# lednode.net
KiCad netlist of a schematic drawn in EAGLE
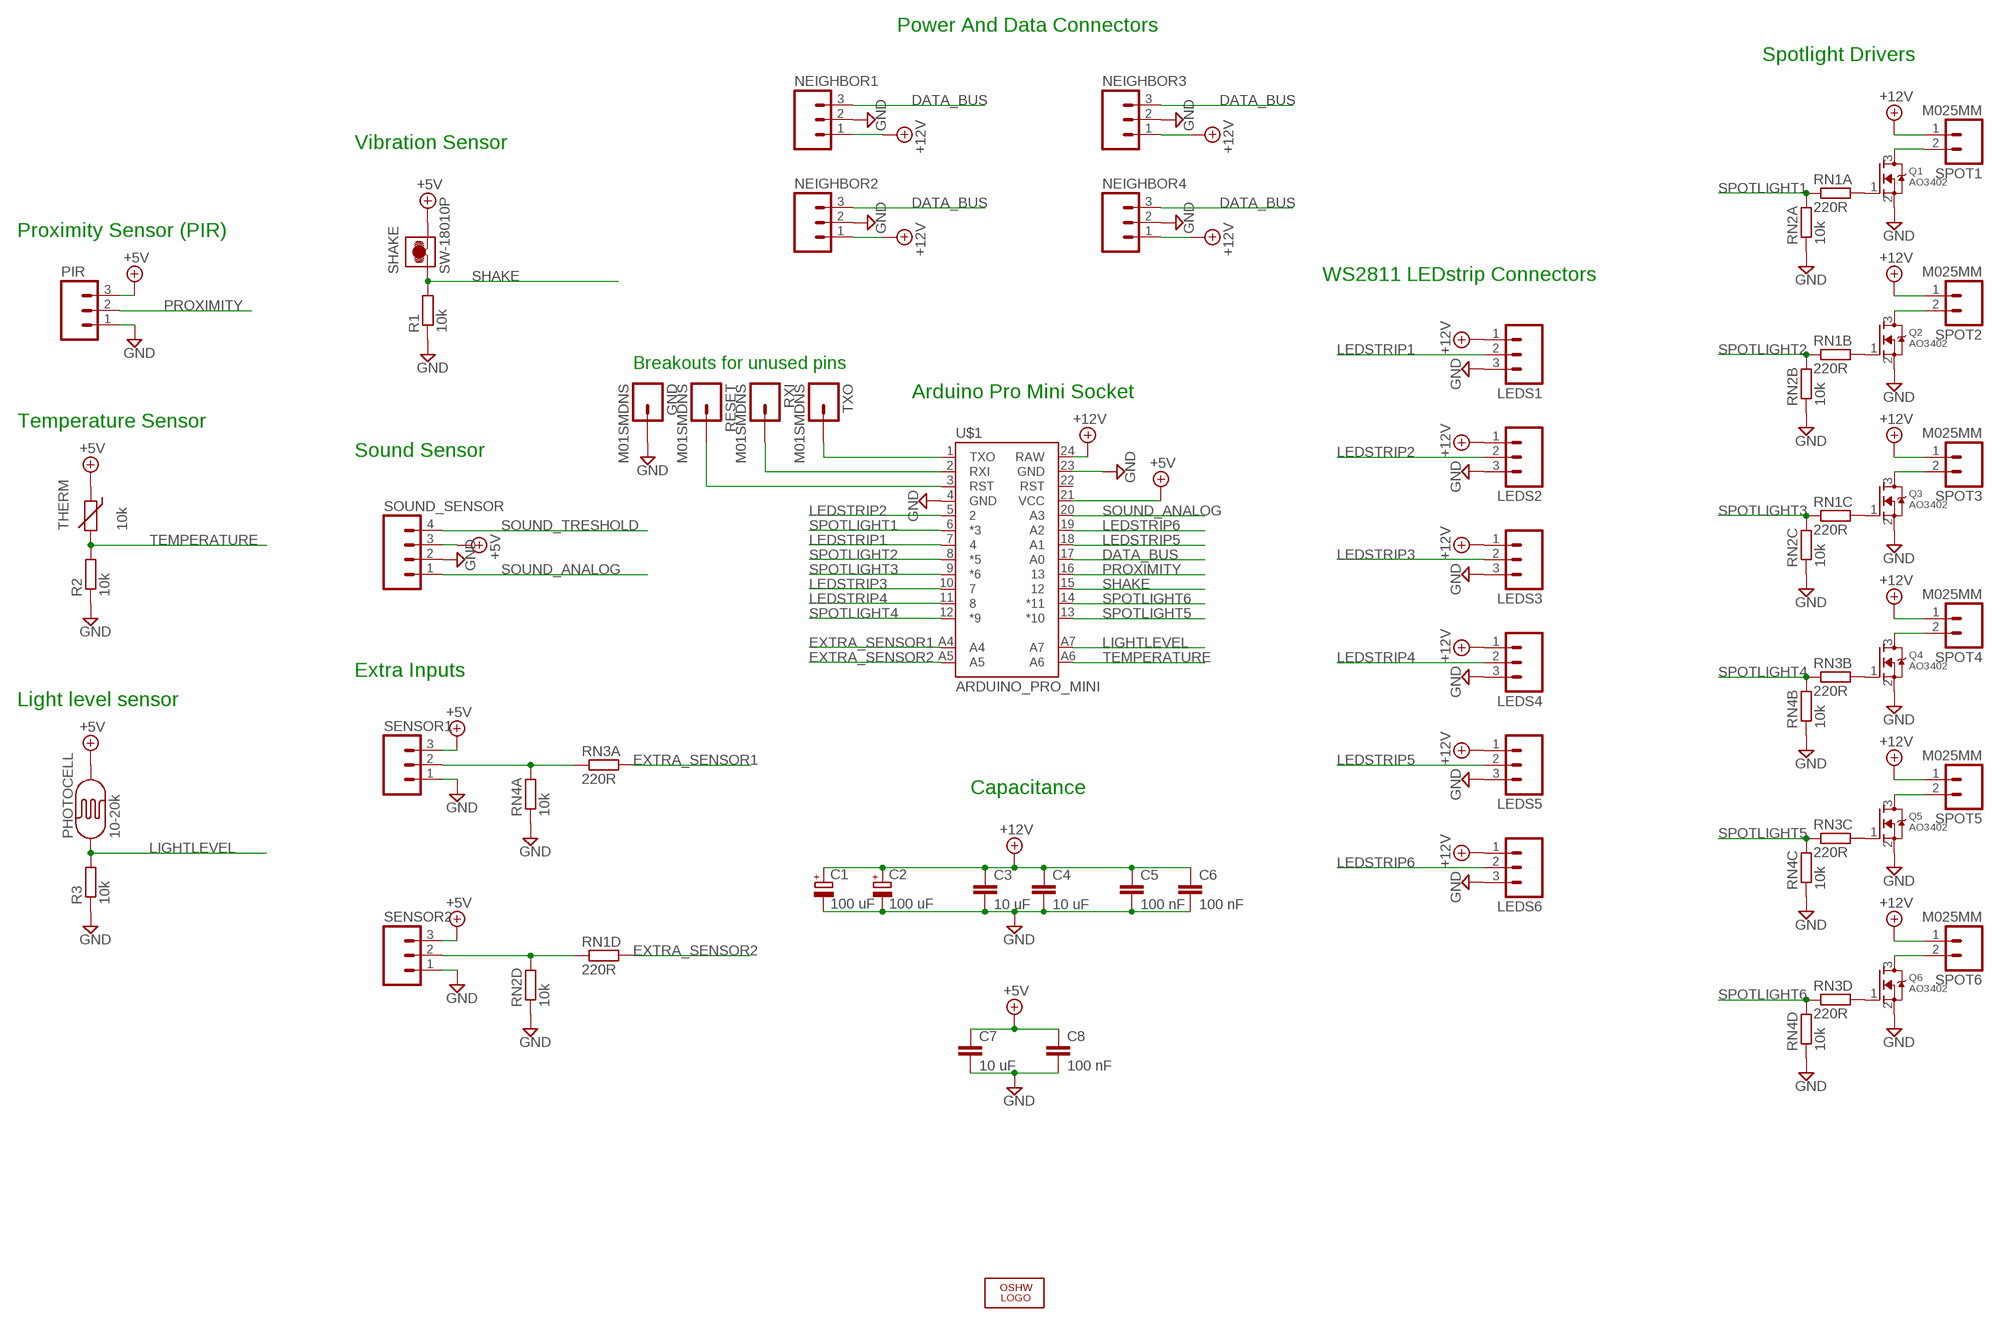
[diagram p0: schematic, sheet 1]

(export (version "E")
  (design (tool "Eeschema 10.0.6"))
  (components
    (comp (ref "C1")
      (value "100 uF")
      (footprint "eagle-import:E3,5-10")
      (libsource (lib "eagle-import") (part "CPOL-EUE3.5-10"))
    )
    (comp (ref "C2")
      (value "100 uF")
      (footprint "eagle-import:E3,5-10")
      (libsource (lib "eagle-import") (part "CPOL-EUE3.5-10"))
    )
    (comp (ref "C3")
      (value "10 uF")
      (footprint "eagle-import:C1206")
      (libsource (lib "eagle-import") (part "C-EUC1206"))
    )
    (comp (ref "C4")
      (value "10 uF")
      (footprint "eagle-import:C1206")
      (libsource (lib "eagle-import") (part "C-EUC1206"))
    )
    (comp (ref "C5")
      (value "100 nF")
      (footprint "eagle-import:C0805")
      (libsource (lib "eagle-import") (part "C-EUC0805"))
    )
    (comp (ref "C6")
      (value "100 nF")
      (footprint "eagle-import:C0805")
      (libsource (lib "eagle-import") (part "C-EUC0805"))
    )
    (comp (ref "C7")
      (value "10 uF")
      (footprint "eagle-import:C1206")
      (libsource (lib "eagle-import") (part "C-EUC1206"))
    )
    (comp (ref "C8")
      (value "100 nF")
      (footprint "eagle-import:C0805")
      (libsource (lib "eagle-import") (part "C-EUC0805"))
    )
    (comp (ref "GND")
      (value "M01SMDNS")
      (footprint "eagle-import:1X01NS")
      (libsource (lib "eagle-import") (part "M01SMDNS"))
    )
    (comp (ref "LEDS1")
      (value "M03LONGPADS")
      (footprint "eagle-import:1X03_LONGPADS")
      (libsource (lib "eagle-import") (part "M03LONGPADS"))
    )
    (comp (ref "LEDS2")
      (value "M03LONGPADS")
      (footprint "eagle-import:1X03_LONGPADS")
      (libsource (lib "eagle-import") (part "M03LONGPADS"))
    )
    (comp (ref "LEDS3")
      (value "M03LONGPADS")
      (footprint "eagle-import:1X03_LONGPADS")
      (libsource (lib "eagle-import") (part "M03LONGPADS"))
    )
    (comp (ref "LEDS4")
      (value "M03LONGPADS")
      (footprint "eagle-import:1X03_LONGPADS")
      (libsource (lib "eagle-import") (part "M03LONGPADS"))
    )
    (comp (ref "LEDS5")
      (value "M03LONGPADS")
      (footprint "eagle-import:1X03_LONGPADS")
      (libsource (lib "eagle-import") (part "M03LONGPADS"))
    )
    (comp (ref "LEDS6")
      (value "M03LONGPADS")
      (footprint "eagle-import:1X03_LONGPADS")
      (libsource (lib "eagle-import") (part "M03LONGPADS"))
    )
    (comp (ref "LOGO3")
      (value "LOGO-OSHW-8MILX0100-NT")
      (footprint "eagle-import:OSHW_8X100_NOTEXT")
      (libsource (lib "eagle-import") (part "LOGO-OSHW-8MILX0100-NT"))
    )
    (comp (ref "NEIGHBOR1")
      (value "M03-SCREW-5MM")
      (footprint "eagle-import:SCREWTERMINAL-5MM-3")
      (libsource (lib "eagle-import") (part "M03-SCREW-5MM"))
    )
    (comp (ref "NEIGHBOR2")
      (value "M03-SCREW-5MM")
      (footprint "eagle-import:SCREWTERMINAL-5MM-3")
      (libsource (lib "eagle-import") (part "M03-SCREW-5MM"))
    )
    (comp (ref "NEIGHBOR3")
      (value "M03-SCREW-5MM")
      (footprint "eagle-import:SCREWTERMINAL-5MM-3")
      (libsource (lib "eagle-import") (part "M03-SCREW-5MM"))
    )
    (comp (ref "NEIGHBOR4")
      (value "M03-SCREW-5MM")
      (footprint "eagle-import:SCREWTERMINAL-5MM-3")
      (libsource (lib "eagle-import") (part "M03-SCREW-5MM"))
    )
    (comp (ref "PHOTOCELL")
      (value "10-20k")
      (footprint "eagle-import:PHOTOCELL")
      (libsource (lib "eagle-import") (part "PHOTOCELLPTH"))
    )
    (comp (ref "PIR")
      (value "M03PTH")
      (footprint "eagle-import:1X03")
      (libsource (lib "eagle-import") (part "M03PTH"))
    )
    (comp (ref "Q1")
      (value "AO3402")
      (footprint "eagle-import:SOT23-W")
      (libsource (lib "eagle-import") (part "MOSFET-NWAVE"))
    )
    (comp (ref "Q2")
      (value "AO3402")
      (footprint "eagle-import:SOT23-W")
      (libsource (lib "eagle-import") (part "MOSFET-NWAVE"))
    )
    (comp (ref "Q3")
      (value "AO3402")
      (footprint "eagle-import:SOT23-W")
      (libsource (lib "eagle-import") (part "MOSFET-NWAVE"))
    )
    (comp (ref "Q4")
      (value "AO3402")
      (footprint "eagle-import:SOT23-W")
      (libsource (lib "eagle-import") (part "MOSFET-NWAVE"))
    )
    (comp (ref "Q5")
      (value "AO3402")
      (footprint "eagle-import:SOT23-W")
      (libsource (lib "eagle-import") (part "MOSFET-NWAVE"))
    )
    (comp (ref "Q6")
      (value "AO3402")
      (footprint "eagle-import:SOT23-W")
      (libsource (lib "eagle-import") (part "MOSFET-NWAVE"))
    )
    (comp (ref "R1")
      (value "10k")
      (footprint "eagle-import:R0805")
      (libsource (lib "eagle-import") (part "R-EU_R0805"))
    )
    (comp (ref "R2")
      (value "10k")
      (footprint "eagle-import:R0805")
      (libsource (lib "eagle-import") (part "R-EU_R0805"))
    )
    (comp (ref "R3")
      (value "10k")
      (footprint "eagle-import:R0805")
      (libsource (lib "eagle-import") (part "R-EU_R0805"))
    )
    (comp (ref "RESET")
      (value "M01SMDNS")
      (footprint "eagle-import:1X01NS")
      (libsource (lib "eagle-import") (part "M01SMDNS"))
    )
    (comp (ref "RN1")
      (value "220R")
      (footprint "eagle-import:RN8P-4R-CRA06S")
      (libsource (lib "eagle-import") (part "RESISTOR_ARRAY_4"))
    )
    (comp (ref "RN2")
      (value "10k")
      (footprint "eagle-import:RN8P-4R-CRA06S")
      (libsource (lib "eagle-import") (part "RESISTOR_ARRAY_4"))
    )
    (comp (ref "RN3")
      (value "220R")
      (footprint "eagle-import:RN8P-4R-CRA06S")
      (libsource (lib "eagle-import") (part "RESISTOR_ARRAY_4"))
    )
    (comp (ref "RN4")
      (value "10k")
      (footprint "eagle-import:RN8P-4R-CRA06S")
      (libsource (lib "eagle-import") (part "RESISTOR_ARRAY_4"))
    )
    (comp (ref "RXI")
      (value "M01SMDNS")
      (footprint "eagle-import:1X01NS")
      (libsource (lib "eagle-import") (part "M01SMDNS"))
    )
    (comp (ref "SENSOR1")
      (value "M03PTH")
      (footprint "eagle-import:1X03")
      (libsource (lib "eagle-import") (part "M03PTH"))
    )
    (comp (ref "SENSOR2")
      (value "M03PTH")
      (footprint "eagle-import:1X03")
      (libsource (lib "eagle-import") (part "M03PTH"))
    )
    (comp (ref "SHAKE")
      (value "SW-18010P")
      (footprint "eagle-import:CM4400")
      (fields (field (name "MF") "FARNELL") (field (name "MPN") "CM4400-1."))
      (libsource (lib "eagle-import") (part "CM4400"))
    )
    (comp (ref "SOUND_SENSOR")
      (value "M041X04_NO_SILK")
      (footprint "eagle-import:1X04_NO_SILK")
      (libsource (lib "eagle-import") (part "M041X04_NO_SILK"))
    )
    (comp (ref "SPOT1")
      (value "M025MM")
      (footprint "eagle-import:SCREWTERMINAL-5MM-2")
      (libsource (lib "eagle-import") (part "M025MM"))
    )
    (comp (ref "SPOT2")
      (value "M025MM")
      (footprint "eagle-import:SCREWTERMINAL-5MM-2")
      (libsource (lib "eagle-import") (part "M025MM"))
    )
    (comp (ref "SPOT3")
      (value "M025MM")
      (footprint "eagle-import:SCREWTERMINAL-5MM-2")
      (libsource (lib "eagle-import") (part "M025MM"))
    )
    (comp (ref "SPOT4")
      (value "M025MM")
      (footprint "eagle-import:SCREWTERMINAL-5MM-2")
      (libsource (lib "eagle-import") (part "M025MM"))
    )
    (comp (ref "SPOT5")
      (value "M025MM")
      (footprint "eagle-import:SCREWTERMINAL-5MM-2")
      (libsource (lib "eagle-import") (part "M025MM"))
    )
    (comp (ref "SPOT6")
      (value "M025MM")
      (footprint "eagle-import:SCREWTERMINAL-5MM-2")
      (libsource (lib "eagle-import") (part "M025MM"))
    )
    (comp (ref "THERM")
      (value "10k")
      (footprint "eagle-import:R-7,5")
      (libsource (lib "eagle-import") (part "THERMISTOR_R-7,5"))
    )
    (comp (ref "TXO")
      (value "M01SMDNS")
      (footprint "eagle-import:1X01NS")
      (libsource (lib "eagle-import") (part "M01SMDNS"))
    )
    (comp (ref "U$1")
      (value "ARDUINO_PRO_MINI")
      (footprint "eagle-import:ARDUINO_PRO_MINI")
      (libsource (lib "eagle-import") (part "ARDUINO_PRO_MINI"))
    )
  )
  (nets
    (net (code "1") (name "+5V") (class "Default")
      (node (ref "C7") (pin "1") (pinfunction "1_1") (pintype "passive"))
      (node (ref "C8") (pin "1") (pinfunction "1_1") (pintype "passive"))
      (node (ref "PHOTOCELL") (pin "2") (pinfunction "P$2_2") (pintype "bidirectional"))
      (node (ref "PIR") (pin "3") (pinfunction "3_3") (pintype "passive"))
      (node (ref "SENSOR1") (pin "3") (pinfunction "3_3") (pintype "passive"))
      (node (ref "SENSOR2") (pin "3") (pinfunction "3_3") (pintype "passive"))
      (node (ref "SHAKE") (pin "2") (pinfunction "2_2") (pintype "passive"))
      (node (ref "SOUND_SENSOR") (pin "3") (pinfunction "3_3") (pintype "passive"))
      (node (ref "THERM") (pin "1") (pinfunction "1_1") (pintype "passive"))
      (node (ref "U$1") (pin "21") (pinfunction "VCC_21") (pintype "bidirectional"))
    )
    (net (code "2") (name "+12V") (class "Default")
      (node (ref "C1") (pin "+") (pinfunction "+_+") (pintype "passive"))
      (node (ref "C2") (pin "+") (pinfunction "+_+") (pintype "passive"))
      (node (ref "C3") (pin "1") (pinfunction "1_1") (pintype "passive"))
      (node (ref "C4") (pin "1") (pinfunction "1_1") (pintype "passive"))
      (node (ref "C5") (pin "1") (pinfunction "1_1") (pintype "passive"))
      (node (ref "C6") (pin "1") (pinfunction "1_1") (pintype "passive"))
      (node (ref "LEDS1") (pin "1") (pinfunction "1_1") (pintype "passive"))
      (node (ref "LEDS2") (pin "1") (pinfunction "1_1") (pintype "passive"))
      (node (ref "LEDS3") (pin "1") (pinfunction "1_1") (pintype "passive"))
      (node (ref "LEDS4") (pin "1") (pinfunction "1_1") (pintype "passive"))
      (node (ref "LEDS5") (pin "1") (pinfunction "1_1") (pintype "passive"))
      (node (ref "LEDS6") (pin "1") (pinfunction "1_1") (pintype "passive"))
      (node (ref "NEIGHBOR1") (pin "1") (pinfunction "1_1") (pintype "passive"))
      (node (ref "NEIGHBOR2") (pin "1") (pinfunction "1_1") (pintype "passive"))
      (node (ref "NEIGHBOR3") (pin "1") (pinfunction "1_1") (pintype "passive"))
      (node (ref "NEIGHBOR4") (pin "1") (pinfunction "1_1") (pintype "passive"))
      (node (ref "SPOT1") (pin "1") (pinfunction "1_1") (pintype "passive"))
      (node (ref "SPOT2") (pin "1") (pinfunction "1_1") (pintype "passive"))
      (node (ref "SPOT3") (pin "1") (pinfunction "1_1") (pintype "passive"))
      (node (ref "SPOT4") (pin "1") (pinfunction "1_1") (pintype "passive"))
      (node (ref "SPOT5") (pin "1") (pinfunction "1_1") (pintype "passive"))
      (node (ref "SPOT6") (pin "1") (pinfunction "1_1") (pintype "passive"))
      (node (ref "U$1") (pin "24") (pinfunction "RAW_24") (pintype "bidirectional"))
    )
    (net (code "3") (name "/DATA_BUS") (class "Default")
      (node (ref "NEIGHBOR1") (pin "3") (pinfunction "3_3") (pintype "passive"))
      (node (ref "NEIGHBOR2") (pin "3") (pinfunction "3_3") (pintype "passive"))
      (node (ref "NEIGHBOR3") (pin "3") (pinfunction "3_3") (pintype "passive"))
      (node (ref "NEIGHBOR4") (pin "3") (pinfunction "3_3") (pintype "passive"))
      (node (ref "U$1") (pin "17") (pinfunction "A0_17") (pintype "bidirectional"))
    )
    (net (code "4") (name "/EXTRA_SENSOR1") (class "Default")
      (node (ref "RN3") (pin "8") (pinfunction "2_8") (pintype "passive"))
      (node (ref "U$1") (pin "A4") (pinfunction "A4_A4") (pintype "bidirectional"))
    )
    (net (code "5") (name "/EXTRA_SENSOR2") (class "Default")
      (node (ref "RN1") (pin "5") (pinfunction "2_5") (pintype "passive"))
      (node (ref "U$1") (pin "A5") (pinfunction "A5_A5") (pintype "bidirectional"))
    )
    (net (code "6") (name "/LEDSTRIP1") (class "Default")
      (node (ref "LEDS1") (pin "2") (pinfunction "2_2") (pintype "passive"))
      (node (ref "U$1") (pin "7") (pinfunction "4_7") (pintype "bidirectional"))
    )
    (net (code "7") (name "/LEDSTRIP2") (class "Default")
      (node (ref "LEDS2") (pin "2") (pinfunction "2_2") (pintype "passive"))
      (node (ref "U$1") (pin "5") (pinfunction "2_5") (pintype "bidirectional"))
    )
    (net (code "8") (name "/LEDSTRIP3") (class "Default")
      (node (ref "LEDS3") (pin "2") (pinfunction "2_2") (pintype "passive"))
      (node (ref "U$1") (pin "10") (pinfunction "7_10") (pintype "bidirectional"))
    )
    (net (code "9") (name "/LEDSTRIP4") (class "Default")
      (node (ref "LEDS4") (pin "2") (pinfunction "2_2") (pintype "passive"))
      (node (ref "U$1") (pin "11") (pinfunction "8_11") (pintype "bidirectional"))
    )
    (net (code "10") (name "/LEDSTRIP5") (class "Default")
      (node (ref "LEDS5") (pin "2") (pinfunction "2_2") (pintype "passive"))
      (node (ref "U$1") (pin "18") (pinfunction "A1_18") (pintype "bidirectional"))
    )
    (net (code "11") (name "/LEDSTRIP6") (class "Default")
      (node (ref "LEDS6") (pin "2") (pinfunction "2_2") (pintype "passive"))
      (node (ref "U$1") (pin "19") (pinfunction "A2_19") (pintype "bidirectional"))
    )
    (net (code "12") (name "/LIGHTLEVEL") (class "Default")
      (node (ref "PHOTOCELL") (pin "1") (pinfunction "P$1_1") (pintype "bidirectional"))
      (node (ref "R3") (pin "2") (pinfunction "2_2") (pintype "passive"))
      (node (ref "U$1") (pin "A7") (pinfunction "A7_A7") (pintype "bidirectional"))
    )
    (net (code "13") (name "/PROXIMITY") (class "Default")
      (node (ref "PIR") (pin "2") (pinfunction "2_2") (pintype "passive"))
      (node (ref "U$1") (pin "16") (pinfunction "13_16") (pintype "bidirectional"))
    )
    (net (code "14") (name "/SHAKE") (class "Default")
      (node (ref "R1") (pin "2") (pinfunction "2_2") (pintype "passive"))
      (node (ref "SHAKE") (pin "1") (pinfunction "1_1") (pintype "passive"))
      (node (ref "U$1") (pin "15") (pinfunction "12_15") (pintype "bidirectional"))
    )
    (net (code "15") (name "/SOUND_ANALOG") (class "Default")
      (node (ref "SOUND_SENSOR") (pin "1") (pinfunction "1_1") (pintype "passive"))
      (node (ref "U$1") (pin "20") (pinfunction "A3_20") (pintype "bidirectional"))
    )
    (net (code "16") (name "/SOUND_TRESHOLD") (class "Default")
      (node (ref "SOUND_SENSOR") (pin "4") (pinfunction "4_4") (pintype "passive"))
    )
    (net (code "17") (name "/SPOTLIGHT1") (class "Default")
      (node (ref "RN1") (pin "1") (pinfunction "1_1") (pintype "passive"))
      (node (ref "RN2") (pin "8") (pinfunction "2_8") (pintype "passive"))
      (node (ref "U$1") (pin "6") (pinfunction "*3_6") (pintype "bidirectional"))
    )
    (net (code "18") (name "/SPOTLIGHT2") (class "Default")
      (node (ref "RN1") (pin "2") (pinfunction "1_2") (pintype "passive"))
      (node (ref "RN2") (pin "7") (pinfunction "2_7") (pintype "passive"))
      (node (ref "U$1") (pin "8") (pinfunction "*5_8") (pintype "bidirectional"))
    )
    (net (code "19") (name "/SPOTLIGHT3") (class "Default")
      (node (ref "RN1") (pin "3") (pinfunction "1_3") (pintype "passive"))
      (node (ref "RN2") (pin "6") (pinfunction "2_6") (pintype "passive"))
      (node (ref "U$1") (pin "9") (pinfunction "*6_9") (pintype "bidirectional"))
    )
    (net (code "20") (name "/SPOTLIGHT4") (class "Default")
      (node (ref "RN3") (pin "2") (pinfunction "1_2") (pintype "passive"))
      (node (ref "RN4") (pin "7") (pinfunction "2_7") (pintype "passive"))
      (node (ref "U$1") (pin "12") (pinfunction "*9_12") (pintype "bidirectional"))
    )
    (net (code "21") (name "/SPOTLIGHT5") (class "Default")
      (node (ref "RN3") (pin "3") (pinfunction "1_3") (pintype "passive"))
      (node (ref "RN4") (pin "6") (pinfunction "2_6") (pintype "passive"))
      (node (ref "U$1") (pin "13") (pinfunction "*10_13") (pintype "bidirectional"))
    )
    (net (code "22") (name "/SPOTLIGHT6") (class "Default")
      (node (ref "RN3") (pin "4") (pinfunction "1_4") (pintype "passive"))
      (node (ref "RN4") (pin "5") (pinfunction "2_5") (pintype "passive"))
      (node (ref "U$1") (pin "14") (pinfunction "*11_14") (pintype "bidirectional"))
    )
    (net (code "23") (name "/TEMPERATURE") (class "Default")
      (node (ref "R2") (pin "2") (pinfunction "2_2") (pintype "passive"))
      (node (ref "THERM") (pin "2") (pinfunction "2_2") (pintype "passive"))
      (node (ref "U$1") (pin "A6") (pinfunction "A6_A6") (pintype "bidirectional"))
    )
    (net (code "24") (name "GND") (class "Default")
      (node (ref "C1") (pin "-") (pinfunction "-_-") (pintype "passive"))
      (node (ref "C2") (pin "-") (pinfunction "-_-") (pintype "passive"))
      (node (ref "C3") (pin "2") (pinfunction "2_2") (pintype "passive"))
      (node (ref "C4") (pin "2") (pinfunction "2_2") (pintype "passive"))
      (node (ref "C5") (pin "2") (pinfunction "2_2") (pintype "passive"))
      (node (ref "C6") (pin "2") (pinfunction "2_2") (pintype "passive"))
      (node (ref "C7") (pin "2") (pinfunction "2_2") (pintype "passive"))
      (node (ref "C8") (pin "2") (pinfunction "2_2") (pintype "passive"))
      (node (ref "GND") (pin "1") (pinfunction "1_1") (pintype "passive"))
      (node (ref "LEDS1") (pin "3") (pinfunction "3_3") (pintype "passive"))
      (node (ref "LEDS2") (pin "3") (pinfunction "3_3") (pintype "passive"))
      (node (ref "LEDS3") (pin "3") (pinfunction "3_3") (pintype "passive"))
      (node (ref "LEDS4") (pin "3") (pinfunction "3_3") (pintype "passive"))
      (node (ref "LEDS5") (pin "3") (pinfunction "3_3") (pintype "passive"))
      (node (ref "LEDS6") (pin "3") (pinfunction "3_3") (pintype "passive"))
      (node (ref "NEIGHBOR1") (pin "2") (pinfunction "2_2") (pintype "passive"))
      (node (ref "NEIGHBOR2") (pin "2") (pinfunction "2_2") (pintype "passive"))
      (node (ref "NEIGHBOR3") (pin "2") (pinfunction "2_2") (pintype "passive"))
      (node (ref "NEIGHBOR4") (pin "2") (pinfunction "2_2") (pintype "passive"))
      (node (ref "PIR") (pin "1") (pinfunction "1_1") (pintype "passive"))
      (node (ref "Q1") (pin "2") (pinfunction "S_2") (pintype "bidirectional"))
      (node (ref "Q2") (pin "2") (pinfunction "S_2") (pintype "bidirectional"))
      (node (ref "Q3") (pin "2") (pinfunction "S_2") (pintype "bidirectional"))
      (node (ref "Q4") (pin "2") (pinfunction "S_2") (pintype "bidirectional"))
      (node (ref "Q5") (pin "2") (pinfunction "S_2") (pintype "bidirectional"))
      (node (ref "Q6") (pin "2") (pinfunction "S_2") (pintype "bidirectional"))
      (node (ref "R1") (pin "1") (pinfunction "1_1") (pintype "passive"))
      (node (ref "R2") (pin "1") (pinfunction "1_1") (pintype "passive"))
      (node (ref "R3") (pin "1") (pinfunction "1_1") (pintype "passive"))
      (node (ref "RN2") (pin "1") (pinfunction "1_1") (pintype "passive"))
      (node (ref "RN2") (pin "2") (pinfunction "1_2") (pintype "passive"))
      (node (ref "RN2") (pin "3") (pinfunction "1_3") (pintype "passive"))
      (node (ref "RN2") (pin "4") (pinfunction "1_4") (pintype "passive"))
      (node (ref "RN4") (pin "1") (pinfunction "1_1") (pintype "passive"))
      (node (ref "RN4") (pin "2") (pinfunction "1_2") (pintype "passive"))
      (node (ref "RN4") (pin "3") (pinfunction "1_3") (pintype "passive"))
      (node (ref "RN4") (pin "4") (pinfunction "1_4") (pintype "passive"))
      (node (ref "SENSOR1") (pin "1") (pinfunction "1_1") (pintype "passive"))
      (node (ref "SENSOR2") (pin "1") (pinfunction "1_1") (pintype "passive"))
      (node (ref "SOUND_SENSOR") (pin "2") (pinfunction "2_2") (pintype "passive"))
      (node (ref "U$1") (pin "23") (pinfunction "GND_23") (pintype "bidirectional"))
      (node (ref "U$1") (pin "4") (pinfunction "GND_4") (pintype "bidirectional"))
    )
    (net (code "25") (name "Net-(Q1-D)") (class "Default")
      (node (ref "Q1") (pin "3") (pinfunction "D_3") (pintype "bidirectional"))
      (node (ref "SPOT1") (pin "2") (pinfunction "2_2") (pintype "passive"))
    )
    (net (code "26") (name "Net-(Q1-G)") (class "Default")
      (node (ref "Q1") (pin "1") (pinfunction "G_1") (pintype "bidirectional"))
      (node (ref "RN1") (pin "8") (pinfunction "2_8") (pintype "passive"))
    )
    (net (code "27") (name "Net-(Q2-D)") (class "Default")
      (node (ref "Q2") (pin "3") (pinfunction "D_3") (pintype "bidirectional"))
      (node (ref "SPOT2") (pin "2") (pinfunction "2_2") (pintype "passive"))
    )
    (net (code "28") (name "Net-(Q2-G)") (class "Default")
      (node (ref "Q2") (pin "1") (pinfunction "G_1") (pintype "bidirectional"))
      (node (ref "RN1") (pin "7") (pinfunction "2_7") (pintype "passive"))
    )
    (net (code "29") (name "Net-(Q3-D)") (class "Default")
      (node (ref "Q3") (pin "3") (pinfunction "D_3") (pintype "bidirectional"))
      (node (ref "SPOT3") (pin "2") (pinfunction "2_2") (pintype "passive"))
    )
    (net (code "30") (name "Net-(Q3-G)") (class "Default")
      (node (ref "Q3") (pin "1") (pinfunction "G_1") (pintype "bidirectional"))
      (node (ref "RN1") (pin "6") (pinfunction "2_6") (pintype "passive"))
    )
    (net (code "31") (name "Net-(Q4-D)") (class "Default")
      (node (ref "Q4") (pin "3") (pinfunction "D_3") (pintype "bidirectional"))
      (node (ref "SPOT4") (pin "2") (pinfunction "2_2") (pintype "passive"))
    )
    (net (code "32") (name "Net-(Q4-G)") (class "Default")
      (node (ref "Q4") (pin "1") (pinfunction "G_1") (pintype "bidirectional"))
      (node (ref "RN3") (pin "7") (pinfunction "2_7") (pintype "passive"))
    )
    (net (code "33") (name "Net-(Q5-D)") (class "Default")
      (node (ref "Q5") (pin "3") (pinfunction "D_3") (pintype "bidirectional"))
      (node (ref "SPOT5") (pin "2") (pinfunction "2_2") (pintype "passive"))
    )
    (net (code "34") (name "Net-(Q5-G)") (class "Default")
      (node (ref "Q5") (pin "1") (pinfunction "G_1") (pintype "bidirectional"))
      (node (ref "RN3") (pin "6") (pinfunction "2_6") (pintype "passive"))
    )
    (net (code "35") (name "Net-(Q6-D)") (class "Default")
      (node (ref "Q6") (pin "3") (pinfunction "D_3") (pintype "bidirectional"))
      (node (ref "SPOT6") (pin "2") (pinfunction "2_2") (pintype "passive"))
    )
    (net (code "36") (name "Net-(Q6-G)") (class "Default")
      (node (ref "Q6") (pin "1") (pinfunction "G_1") (pintype "bidirectional"))
      (node (ref "RN3") (pin "5") (pinfunction "2_5") (pintype "passive"))
    )
    (net (code "37") (name "Net-(RESET-Pad1)") (class "Default")
      (node (ref "RESET") (pin "1") (pinfunction "1_1") (pintype "passive"))
      (node (ref "U$1") (pin "3") (pinfunction "RST_3") (pintype "bidirectional"))
    )
    (net (code "38") (name "Net-(RN1D-1)") (class "Default")
      (node (ref "RN1") (pin "4") (pinfunction "1_4") (pintype "passive"))
      (node (ref "RN2") (pin "5") (pinfunction "2_5") (pintype "passive"))
      (node (ref "SENSOR2") (pin "2") (pinfunction "2_2") (pintype "passive"))
    )
    (net (code "39") (name "Net-(RN4A-2)") (class "Default")
      (node (ref "RN3") (pin "1") (pinfunction "1_1") (pintype "passive"))
      (node (ref "RN4") (pin "8") (pinfunction "2_8") (pintype "passive"))
      (node (ref "SENSOR1") (pin "2") (pinfunction "2_2") (pintype "passive"))
    )
    (net (code "40") (name "Net-(U$1-RXI)") (class "Default")
      (node (ref "RXI") (pin "1") (pinfunction "1_1") (pintype "passive"))
      (node (ref "U$1") (pin "2") (pinfunction "RXI_2") (pintype "bidirectional"))
    )
    (net (code "41") (name "Net-(U$1-TXO)") (class "Default")
      (node (ref "TXO") (pin "1") (pinfunction "1_1") (pintype "passive"))
      (node (ref "U$1") (pin "1") (pinfunction "TXO_1") (pintype "bidirectional"))
    )
    (net (code "42") (name "unconnected-(U$1-RST-Pad22)") (class "Default")
      (node (ref "U$1") (pin "22") (pinfunction "RST_22") (pintype "bidirectional"))
    )
  )
)
